# SolarPwrOptions.net
KiCad netlist of a schematic drawn in EAGLE
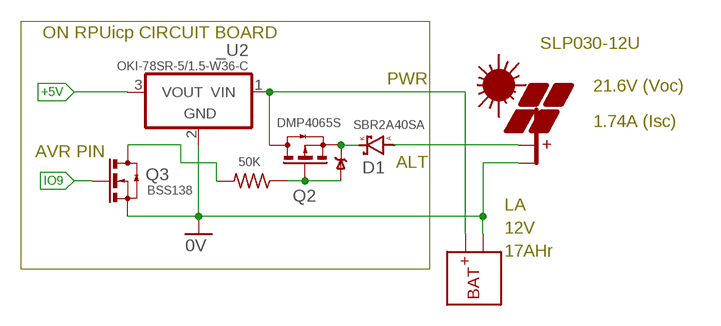
[diagram p0: schematic, sheet 1]

(export (version "E")
  (design (tool "Eeschema 10.0.6"))
  (components
    (comp (ref "D1")
      (value "SBR2A40SA")
      (footprint "eagle-import:SMB")
      (libsource (lib "eagle-import") (part "DSMB"))
    )
    (comp (ref "D3")
      (value "TVSSMC")
      (footprint "eagle-import:SMC")
      (libsource (lib "eagle-import") (part "TVSSMC"))
    )
    (comp (ref "PV2")
      (value "PV")
      (footprint "eagle-import:NA-30")
      (libsource (lib "eagle-import") (part "PV"))
    )
    (comp (ref "Q2")
      (value "DMP4065S")
      (footprint "eagle-import:DPAK")
      (libsource (lib "eagle-import") (part "Q-PCH_N-CH?DPAK"))
    )
    (comp (ref "Q3")
      (value "BSS138")
      (footprint "eagle-import:DPAK")
      (libsource (lib "eagle-import") (part "N-CH?DPAK"))
    )
    (comp (ref "R2")
      (value "50K")
      (footprint "eagle-import:C0805(2012)")
      (libsource (lib "eagle-import") (part "R0805"))
    )
    (comp (ref "U$1")
      (value "BAT")
      (footprint "eagle-import:NA-30")
      (libsource (lib "eagle-import") (part "BAT"))
    )
    (comp (ref "_U2")
      (value "OKI-78SR-5/1.5-W36-C")
      (footprint "eagle-import:OKI-78SR-H")
      (libsource (lib "eagle-import") (part "OKI-78SR-H"))
    )
  )
  (nets
    (net (code "1") (name "+5V") (class "Default")
      (node (ref "_U2") (pin "3") (pinfunction "VOUT_3") (pintype "passive"))
    )
    (net (code "2") (name "0V") (class "Default")
      (node (ref "PV2") (pin "2") (pinfunction "-PV_2") (pintype "bidirectional"))
      (node (ref "Q3") (pin "3") (pinfunction "S_3") (pintype "passive"))
      (node (ref "U$1") (pin "2") (pinfunction "-BAT_2") (pintype "bidirectional"))
      (node (ref "_U2") (pin "2") (pinfunction "GND_2") (pintype "passive"))
    )
    (net (code "3") (name "IO9") (class "Default")
      (node (ref "Q3") (pin "1") (pinfunction "G_1") (pintype "passive"))
    )
    (net (code "4") (name "Net-(PV2-+PV)") (class "Default")
      (node (ref "D1") (pin "A") (pinfunction "A_A") (pintype "passive"))
      (node (ref "PV2") (pin "1") (pinfunction "+PV_1") (pintype "bidirectional"))
    )
    (net (code "5") (name "Net-(Q2-D)") (class "Default")
      (node (ref "Q2") (pin "SINK") (pinfunction "D_SINK") (pintype "passive"))
      (node (ref "U$1") (pin "1") (pinfunction "+BAT_1") (pintype "bidirectional"))
      (node (ref "_U2") (pin "1") (pinfunction "VIN_1") (pintype "passive"))
    )
    (net (code "6") (name "Net-(Q2-G)") (class "Default")
      (node (ref "D3") (pin "A") (pinfunction "A_A") (pintype "passive"))
      (node (ref "Q2") (pin "1") (pinfunction "G_1") (pintype "passive"))
      (node (ref "R2") (pin "1") (pinfunction "1_1") (pintype "passive"))
    )
    (net (code "7") (name "Net-(Q2-S)") (class "Default")
      (node (ref "D1") (pin "K") (pinfunction "K_K") (pintype "passive"))
      (node (ref "D3") (pin "C") (pinfunction "C_C") (pintype "passive"))
      (node (ref "Q2") (pin "3") (pinfunction "S_3") (pintype "passive"))
    )
    (net (code "8") (name "Net-(Q3-D)") (class "Default")
      (node (ref "Q3") (pin "SINK") (pinfunction "D_SINK") (pintype "passive"))
      (node (ref "R2") (pin "2") (pinfunction "2_2") (pintype "passive"))
    )
  )
)
